# buoi121.net
KiCad netlist of a schematic drawn in Altium Designer
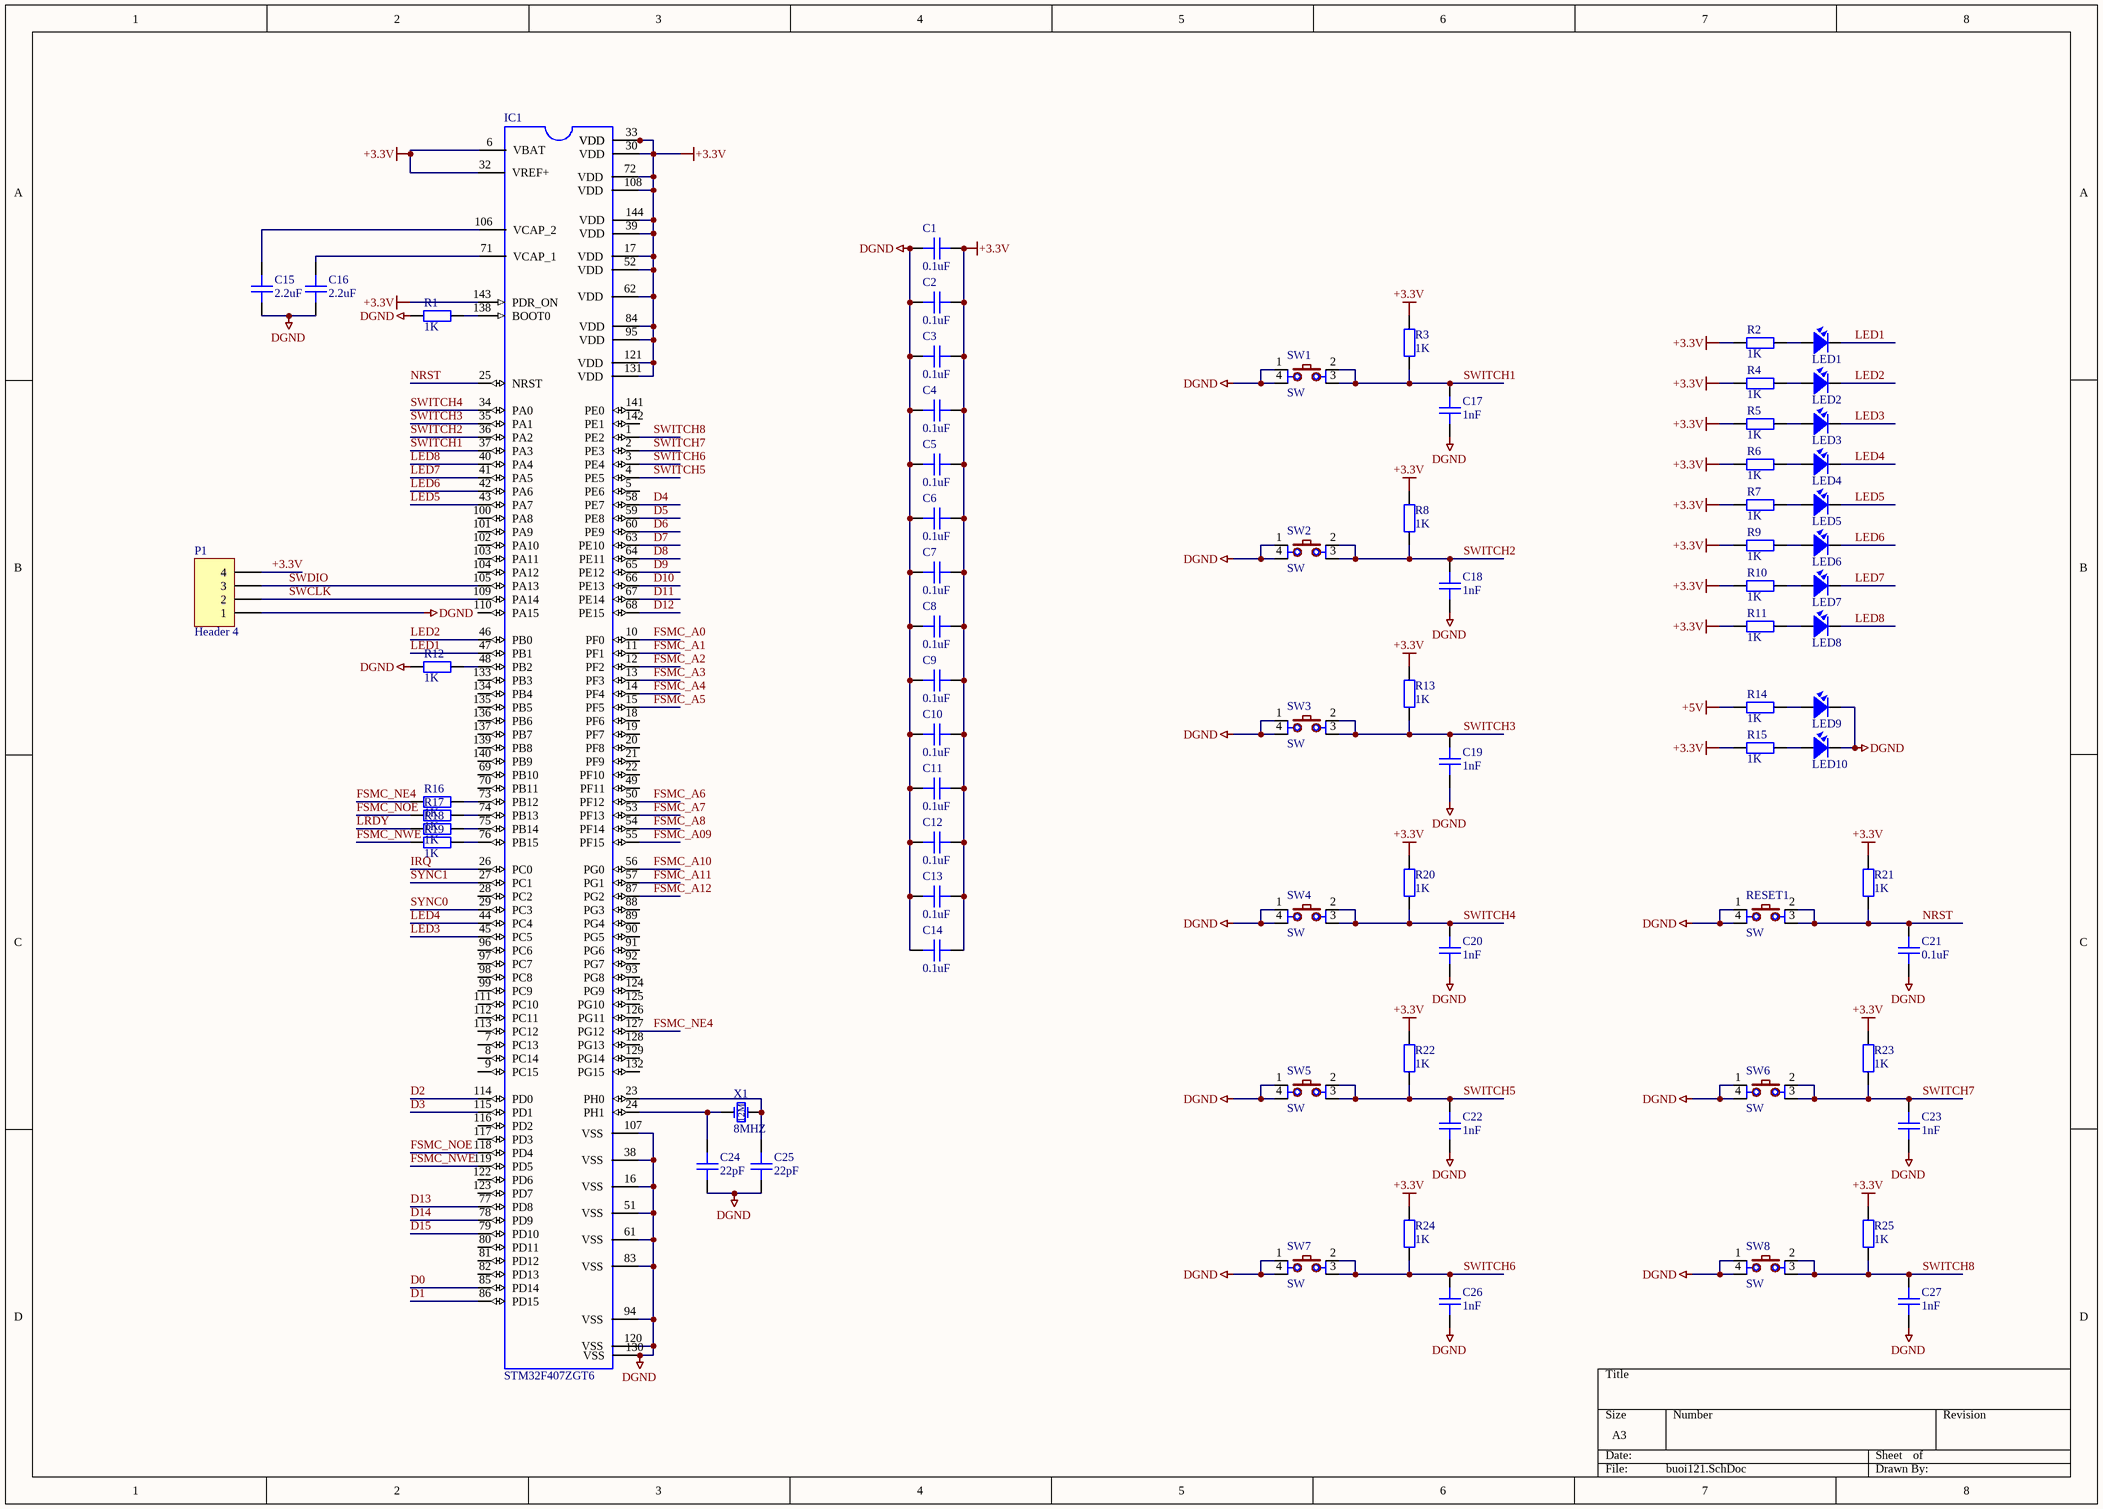
[diagram p0: buoi121.SchDoc]

(export (version "E")
  (design (tool "Eeschema 10.0.6"))
  (components
    (comp (ref "C1")
      (value "0.1uF")
      (footprint "CAPC-0603 (1608)")
      (description "CAP CER 0.1uF 50V 10% X7R 0603")
      (fields (field (name "MPN") "C0603C104K5RACTU"))
      (libsource (lib "BYTECH_HW_LIB_2019 (1)") (part "C0603C104K5RACTU"))
    )
    (comp (ref "C2")
      (value "0.1uF")
      (footprint "CAPC-0603 (1608)")
      (description "CAP CER 0.1uF 50V 10% X7R 0603")
      (fields (field (name "MPN") "C0603C104K5RACTU"))
      (libsource (lib "BYTECH_HW_LIB_2019 (1)") (part "C0603C104K5RACTU"))
    )
    (comp (ref "C3")
      (value "0.1uF")
      (footprint "CAPC-0603 (1608)")
      (description "CAP CER 0.1uF 50V 10% X7R 0603")
      (fields (field (name "MPN") "C0603C104K5RACTU"))
      (libsource (lib "BYTECH_HW_LIB_2019 (1)") (part "C0603C104K5RACTU"))
    )
    (comp (ref "C4")
      (value "0.1uF")
      (footprint "CAPC-0603 (1608)")
      (description "CAP CER 0.1uF 50V 10% X7R 0603")
      (fields (field (name "MPN") "C0603C104K5RACTU"))
      (libsource (lib "BYTECH_HW_LIB_2019 (1)") (part "C0603C104K5RACTU"))
    )
    (comp (ref "C5")
      (value "0.1uF")
      (footprint "CAPC-0603 (1608)")
      (description "CAP CER 0.1uF 50V 10% X7R 0603")
      (fields (field (name "MPN") "C0603C104K5RACTU"))
      (libsource (lib "BYTECH_HW_LIB_2019 (1)") (part "C0603C104K5RACTU"))
    )
    (comp (ref "C6")
      (value "0.1uF")
      (footprint "CAPC-0603 (1608)")
      (description "CAP CER 0.1uF 50V 10% X7R 0603")
      (fields (field (name "MPN") "C0603C104K5RACTU"))
      (libsource (lib "BYTECH_HW_LIB_2019 (1)") (part "C0603C104K5RACTU"))
    )
    (comp (ref "C7")
      (value "0.1uF")
      (footprint "CAPC-0603 (1608)")
      (description "CAP CER 0.1uF 50V 10% X7R 0603")
      (fields (field (name "MPN") "C0603C104K5RACTU"))
      (libsource (lib "BYTECH_HW_LIB_2019 (1)") (part "C0603C104K5RACTU"))
    )
    (comp (ref "C8")
      (value "0.1uF")
      (footprint "CAPC-0603 (1608)")
      (description "CAP CER 0.1uF 50V 10% X7R 0603")
      (fields (field (name "MPN") "C0603C104K5RACTU"))
      (libsource (lib "BYTECH_HW_LIB_2019 (1)") (part "C0603C104K5RACTU"))
    )
    (comp (ref "C9")
      (value "0.1uF")
      (footprint "CAPC-0603 (1608)")
      (description "CAP CER 0.1uF 50V 10% X7R 0603")
      (fields (field (name "MPN") "C0603C104K5RACTU"))
      (libsource (lib "BYTECH_HW_LIB_2019 (1)") (part "C0603C104K5RACTU"))
    )
    (comp (ref "C10")
      (value "0.1uF")
      (footprint "CAPC-0603 (1608)")
      (description "CAP CER 0.1uF 50V 10% X7R 0603")
      (fields (field (name "MPN") "C0603C104K5RACTU"))
      (libsource (lib "BYTECH_HW_LIB_2019 (1)") (part "C0603C104K5RACTU"))
    )
    (comp (ref "C11")
      (value "0.1uF")
      (footprint "CAPC-0603 (1608)")
      (description "CAP CER 0.1uF 50V 10% X7R 0603")
      (fields (field (name "MPN") "C0603C104K5RACTU"))
      (libsource (lib "BYTECH_HW_LIB_2019 (1)") (part "C0603C104K5RACTU"))
    )
    (comp (ref "C12")
      (value "0.1uF")
      (footprint "CAPC-0603 (1608)")
      (description "CAP CER 0.1uF 50V 10% X7R 0603")
      (fields (field (name "MPN") "C0603C104K5RACTU"))
      (libsource (lib "BYTECH_HW_LIB_2019 (1)") (part "C0603C104K5RACTU"))
    )
    (comp (ref "C13")
      (value "0.1uF")
      (footprint "CAPC-0603 (1608)")
      (description "CAP CER 0.1uF 50V 10% X7R 0603")
      (fields (field (name "MPN") "C0603C104K5RACTU"))
      (libsource (lib "BYTECH_HW_LIB_2019 (1)") (part "C0603C104K5RACTU"))
    )
    (comp (ref "C14")
      (value "0.1uF")
      (footprint "CAPC-0603 (1608)")
      (description "CAP CER 0.1uF 50V 10% X7R 0603")
      (fields (field (name "MPN") "C0603C104K5RACTU"))
      (libsource (lib "BYTECH_HW_LIB_2019 (1)") (part "C0603C104K5RACTU"))
    )
    (comp (ref "C15")
      (value "2.2uF")
      (footprint "CAPC-0603 (1608)")
      (description "CAP CER 0.1uF 50V 10% X7R 0603")
      (fields (field (name "MPN") "C0603C104K5RACTU"))
      (libsource (lib "BYTECH_HW_LIB_2019 (1)") (part "C0603C104K5RACTU"))
    )
    (comp (ref "C16")
      (value "2.2uF")
      (footprint "CAPC-0603 (1608)")
      (description "CAP CER 0.1uF 50V 10% X7R 0603")
      (fields (field (name "MPN") "C0603C104K5RACTU"))
      (libsource (lib "BYTECH_HW_LIB_2019 (1)") (part "C0603C104K5RACTU"))
    )
    (comp (ref "C17")
      (value "1nF")
      (footprint "CAPC-0603 (1608)")
      (description "CAP CER 0.1uF 50V 10% X7R 0603")
      (fields (field (name "MPN") "C0603C104K5RACTU"))
      (libsource (lib "BYTECH_HW_LIB_2019 (1)") (part "C0603C104K5RACTU"))
    )
    (comp (ref "C18")
      (value "1nF")
      (footprint "CAPC-0603 (1608)")
      (description "CAP CER 0.1uF 50V 10% X7R 0603")
      (fields (field (name "MPN") "C0603C104K5RACTU"))
      (libsource (lib "BYTECH_HW_LIB_2019 (1)") (part "C0603C104K5RACTU"))
    )
    (comp (ref "C19")
      (value "1nF")
      (footprint "CAPC-0603 (1608)")
      (description "CAP CER 0.1uF 50V 10% X7R 0603")
      (fields (field (name "MPN") "C0603C104K5RACTU"))
      (libsource (lib "BYTECH_HW_LIB_2019 (1)") (part "C0603C104K5RACTU"))
    )
    (comp (ref "C20")
      (value "1nF")
      (footprint "CAPC-0603 (1608)")
      (description "CAP CER 0.1uF 50V 10% X7R 0603")
      (fields (field (name "MPN") "C0603C104K5RACTU"))
      (libsource (lib "BYTECH_HW_LIB_2019 (1)") (part "C0603C104K5RACTU"))
    )
    (comp (ref "C21")
      (value "0.1uF")
      (footprint "CAPC-0603 (1608)")
      (description "CAP CER 0.1uF 50V 10% X7R 0603")
      (fields (field (name "MPN") "C0603C104K5RACTU"))
      (libsource (lib "BYTECH_HW_LIB_2019 (1)") (part "C0603C104K5RACTU"))
    )
    (comp (ref "C22")
      (value "1nF")
      (footprint "CAPC-0603 (1608)")
      (description "CAP CER 0.1uF 50V 10% X7R 0603")
      (fields (field (name "MPN") "C0603C104K5RACTU"))
      (libsource (lib "BYTECH_HW_LIB_2019 (1)") (part "C0603C104K5RACTU"))
    )
    (comp (ref "C23")
      (value "1nF")
      (footprint "CAPC-0603 (1608)")
      (description "CAP CER 0.1uF 50V 10% X7R 0603")
      (fields (field (name "MPN") "C0603C104K5RACTU"))
      (libsource (lib "BYTECH_HW_LIB_2019 (1)") (part "C0603C104K5RACTU"))
    )
    (comp (ref "C24")
      (value "22pF")
      (footprint "CAPC-0603 (1608)")
      (description "CAP CER 0.1uF 50V 10% X7R 0603")
      (fields (field (name "MPN") "C0603C104K5RACTU"))
      (libsource (lib "BYTECH_HW_LIB_2019 (1)") (part "C0603C104K5RACTU"))
    )
    (comp (ref "C25")
      (value "22pF")
      (footprint "CAPC-0603 (1608)")
      (description "CAP CER 0.1uF 50V 10% X7R 0603")
      (fields (field (name "MPN") "C0603C104K5RACTU"))
      (libsource (lib "BYTECH_HW_LIB_2019 (1)") (part "C0603C104K5RACTU"))
    )
    (comp (ref "C26")
      (value "1nF")
      (footprint "CAPC-0603 (1608)")
      (description "CAP CER 0.1uF 50V 10% X7R 0603")
      (fields (field (name "MPN") "C0603C104K5RACTU"))
      (libsource (lib "BYTECH_HW_LIB_2019 (1)") (part "C0603C104K5RACTU"))
    )
    (comp (ref "C27")
      (value "1nF")
      (footprint "CAPC-0603 (1608)")
      (description "CAP CER 0.1uF 50V 10% X7R 0603")
      (fields (field (name "MPN") "C0603C104K5RACTU"))
      (libsource (lib "BYTECH_HW_LIB_2019 (1)") (part "C0603C104K5RACTU"))
    )
    (comp (ref "IC1")
      (value "STM32F407ZGT6")
      (footprint "PCBComponent_1 - duplicate")
      (libsource (lib "STM32F407ZGT6") (part "STM32"))
    )
    (comp (ref "LED1")
      (value "LED")
      (footprint "LED_0603_BLUE")
      (libsource (lib "TechMT.VN_Lib_Project v2") (part "LED SMD"))
    )
    (comp (ref "LED2")
      (value "LED")
      (footprint "LED_0603_BLUE")
      (libsource (lib "TechMT.VN_Lib_Project v2") (part "LED SMD"))
    )
    (comp (ref "LED3")
      (value "LED")
      (footprint "LED_0603_BLUE")
      (libsource (lib "TechMT.VN_Lib_Project v2") (part "LED SMD"))
    )
    (comp (ref "LED4")
      (value "LED")
      (footprint "LED_0603_BLUE")
      (libsource (lib "TechMT.VN_Lib_Project v2") (part "LED SMD"))
    )
    (comp (ref "LED5")
      (value "LED")
      (footprint "LED_0603_BLUE")
      (libsource (lib "TechMT.VN_Lib_Project v2") (part "LED SMD"))
    )
    (comp (ref "LED6")
      (value "LED")
      (footprint "LED_0603_BLUE")
      (libsource (lib "TechMT.VN_Lib_Project v2") (part "LED SMD"))
    )
    (comp (ref "LED7")
      (value "LED")
      (footprint "LED_0603_BLUE")
      (libsource (lib "TechMT.VN_Lib_Project v2") (part "LED SMD"))
    )
    (comp (ref "LED8")
      (value "LED")
      (footprint "LED_0603_BLUE")
      (libsource (lib "TechMT.VN_Lib_Project v2") (part "LED SMD"))
    )
    (comp (ref "LED9")
      (value "LED")
      (footprint "LED_0603_BLUE")
      (libsource (lib "TechMT.VN_Lib_Project v2") (part "LED SMD"))
    )
    (comp (ref "LED10")
      (value "LED")
      (footprint "LED_0603_BLUE")
      (libsource (lib "TechMT.VN_Lib_Project v2") (part "LED SMD"))
    )
    (comp (ref "P1")
      (value "Header 4")
      (footprint "HDR1X4")
      (description "Header, 4-Pin")
      (fields (field (name "PUBLISHER") "Altium Limited"))
      (libsource (lib "My Library") (part "Header 4"))
    )
    (comp (ref "R1")
      (value "1K")
      (footprint "RESC-0603 (1608)")
      (description "RES SMD 2.2K OHM 1% 1/10W 0603")
      (fields (field (name "MPN") "CRCW06032K20FKEA"))
      (libsource (lib "") (part "CRCW06032K20FKEA_1"))
    )
    (comp (ref "R2")
      (value "1K")
      (footprint "RESC-0603 (1608)")
      (description "RES SMD 2.2K OHM 1% 1/10W 0603")
      (fields (field (name "MPN") "CRCW06032K20FKEA"))
      (libsource (lib "BYTECH_HW_LIB_2019 (1)") (part "CRCW06032K20FKEA"))
    )
    (comp (ref "R3")
      (value "1K")
      (footprint "RESC-0603 (1608)")
      (description "RES SMD 2.2K OHM 1% 1/10W 0603")
      (fields (field (name "MPN") "CRCW06032K20FKEA"))
      (libsource (lib "") (part "CRCW06032K20FKEA_2"))
    )
    (comp (ref "R4")
      (value "1K")
      (footprint "RESC-0603 (1608)")
      (description "RES SMD 2.2K OHM 1% 1/10W 0603")
      (fields (field (name "MPN") "CRCW06032K20FKEA"))
      (libsource (lib "BYTECH_HW_LIB_2019 (1)") (part "CRCW06032K20FKEA"))
    )
    (comp (ref "R5")
      (value "1K")
      (footprint "RESC-0603 (1608)")
      (description "RES SMD 2.2K OHM 1% 1/10W 0603")
      (fields (field (name "MPN") "CRCW06032K20FKEA"))
      (libsource (lib "BYTECH_HW_LIB_2019 (1)") (part "CRCW06032K20FKEA"))
    )
    (comp (ref "R6")
      (value "1K")
      (footprint "RESC-0603 (1608)")
      (description "RES SMD 2.2K OHM 1% 1/10W 0603")
      (fields (field (name "MPN") "CRCW06032K20FKEA"))
      (libsource (lib "BYTECH_HW_LIB_2019 (1)") (part "CRCW06032K20FKEA"))
    )
    (comp (ref "R7")
      (value "1K")
      (footprint "RESC-0603 (1608)")
      (description "RES SMD 2.2K OHM 1% 1/10W 0603")
      (fields (field (name "MPN") "CRCW06032K20FKEA"))
      (libsource (lib "BYTECH_HW_LIB_2019 (1)") (part "CRCW06032K20FKEA"))
    )
    (comp (ref "R8")
      (value "1K")
      (footprint "RESC-0603 (1608)")
      (description "RES SMD 2.2K OHM 1% 1/10W 0603")
      (fields (field (name "MPN") "CRCW06032K20FKEA"))
      (libsource (lib "") (part "CRCW06032K20FKEA_2"))
    )
    (comp (ref "R9")
      (value "1K")
      (footprint "RESC-0603 (1608)")
      (description "RES SMD 2.2K OHM 1% 1/10W 0603")
      (fields (field (name "MPN") "CRCW06032K20FKEA"))
      (libsource (lib "BYTECH_HW_LIB_2019 (1)") (part "CRCW06032K20FKEA"))
    )
    (comp (ref "R10")
      (value "1K")
      (footprint "RESC-0603 (1608)")
      (description "RES SMD 2.2K OHM 1% 1/10W 0603")
      (fields (field (name "MPN") "CRCW06032K20FKEA"))
      (libsource (lib "BYTECH_HW_LIB_2019 (1)") (part "CRCW06032K20FKEA"))
    )
    (comp (ref "R11")
      (value "1K")
      (footprint "RESC-0603 (1608)")
      (description "RES SMD 2.2K OHM 1% 1/10W 0603")
      (fields (field (name "MPN") "CRCW06032K20FKEA"))
      (libsource (lib "BYTECH_HW_LIB_2019 (1)") (part "CRCW06032K20FKEA"))
    )
    (comp (ref "R12")
      (value "1K")
      (footprint "RESC-0603 (1608)")
      (description "RES SMD 2.2K OHM 1% 1/10W 0603")
      (fields (field (name "MPN") "CRCW06032K20FKEA"))
      (libsource (lib "") (part "CRCW06032K20FKEA_1"))
    )
    (comp (ref "R13")
      (value "1K")
      (footprint "RESC-0603 (1608)")
      (description "RES SMD 2.2K OHM 1% 1/10W 0603")
      (fields (field (name "MPN") "CRCW06032K20FKEA"))
      (libsource (lib "") (part "CRCW06032K20FKEA_2"))
    )
    (comp (ref "R14")
      (value "1K")
      (footprint "RESC-0603 (1608)")
      (description "RES SMD 2.2K OHM 1% 1/10W 0603")
      (fields (field (name "MPN") "CRCW06032K20FKEA"))
      (libsource (lib "BYTECH_HW_LIB_2019 (1)") (part "CRCW06032K20FKEA"))
    )
    (comp (ref "R15")
      (value "1K")
      (footprint "RESC-0603 (1608)")
      (description "RES SMD 2.2K OHM 1% 1/10W 0603")
      (fields (field (name "MPN") "CRCW06032K20FKEA"))
      (libsource (lib "BYTECH_HW_LIB_2019 (1)") (part "CRCW06032K20FKEA"))
    )
    (comp (ref "R16")
      (value "1K")
      (footprint "RESC-0603 (1608)")
      (description "RES SMD 2.2K OHM 1% 1/10W 0603")
      (fields (field (name "MPN") "CRCW06032K20FKEA"))
      (libsource (lib "") (part "CRCW06032K20FKEA_1"))
    )
    (comp (ref "R17")
      (value "1K")
      (footprint "RESC-0603 (1608)")
      (description "RES SMD 2.2K OHM 1% 1/10W 0603")
      (fields (field (name "MPN") "CRCW06032K20FKEA"))
      (libsource (lib "") (part "CRCW06032K20FKEA_1"))
    )
    (comp (ref "R18")
      (value "1K")
      (footprint "RESC-0603 (1608)")
      (description "RES SMD 2.2K OHM 1% 1/10W 0603")
      (fields (field (name "MPN") "CRCW06032K20FKEA"))
      (libsource (lib "") (part "CRCW06032K20FKEA_1"))
    )
    (comp (ref "R19")
      (value "1K")
      (footprint "RESC-0603 (1608)")
      (description "RES SMD 2.2K OHM 1% 1/10W 0603")
      (fields (field (name "MPN") "CRCW06032K20FKEA"))
      (libsource (lib "") (part "CRCW06032K20FKEA_1"))
    )
    (comp (ref "R20")
      (value "1K")
      (footprint "RESC-0603 (1608)")
      (description "RES SMD 2.2K OHM 1% 1/10W 0603")
      (fields (field (name "MPN") "CRCW06032K20FKEA"))
      (libsource (lib "") (part "CRCW06032K20FKEA_2"))
    )
    (comp (ref "R21")
      (value "1K")
      (footprint "RESC-0603 (1608)")
      (description "RES SMD 2.2K OHM 1% 1/10W 0603")
      (fields (field (name "MPN") "CRCW06032K20FKEA"))
      (libsource (lib "") (part "CRCW06032K20FKEA_2"))
    )
    (comp (ref "R22")
      (value "1K")
      (footprint "RESC-0603 (1608)")
      (description "RES SMD 2.2K OHM 1% 1/10W 0603")
      (fields (field (name "MPN") "CRCW06032K20FKEA"))
      (libsource (lib "") (part "CRCW06032K20FKEA_2"))
    )
    (comp (ref "R23")
      (value "1K")
      (footprint "RESC-0603 (1608)")
      (description "RES SMD 2.2K OHM 1% 1/10W 0603")
      (fields (field (name "MPN") "CRCW06032K20FKEA"))
      (libsource (lib "") (part "CRCW06032K20FKEA_2"))
    )
    (comp (ref "R24")
      (value "1K")
      (footprint "RESC-0603 (1608)")
      (description "RES SMD 2.2K OHM 1% 1/10W 0603")
      (fields (field (name "MPN") "CRCW06032K20FKEA"))
      (libsource (lib "") (part "CRCW06032K20FKEA_2"))
    )
    (comp (ref "R25")
      (value "1K")
      (footprint "RESC-0603 (1608)")
      (description "RES SMD 2.2K OHM 1% 1/10W 0603")
      (fields (field (name "MPN") "CRCW06032K20FKEA"))
      (libsource (lib "") (part "CRCW06032K20FKEA_2"))
    )
    (comp (ref "RESET1")
      (value "SW")
      (footprint "SW2-SMD")
      (description "Switch button 4 pin")
      (libsource (lib "TechMT.VN_Lib_Project v2") (part "SW4"))
    )
    (comp (ref "SW1")
      (value "SW")
      (footprint "SW2-SMD")
      (description "Switch button 4 pin")
      (libsource (lib "TechMT.VN_Lib_Project v2") (part "SW4"))
    )
    (comp (ref "SW2")
      (value "SW")
      (footprint "SW2-SMD")
      (description "Switch button 4 pin")
      (libsource (lib "TechMT.VN_Lib_Project v2") (part "SW4"))
    )
    (comp (ref "SW3")
      (value "SW")
      (footprint "SW2-SMD")
      (description "Switch button 4 pin")
      (libsource (lib "TechMT.VN_Lib_Project v2") (part "SW4"))
    )
    (comp (ref "SW4")
      (value "SW")
      (footprint "SW2-SMD")
      (description "Switch button 4 pin")
      (libsource (lib "TechMT.VN_Lib_Project v2") (part "SW4"))
    )
    (comp (ref "SW5")
      (value "SW")
      (footprint "SW2-SMD")
      (description "Switch button 4 pin")
      (libsource (lib "TechMT.VN_Lib_Project v2") (part "SW4"))
    )
    (comp (ref "SW6")
      (value "SW")
      (footprint "SW2-SMD")
      (description "Switch button 4 pin")
      (libsource (lib "TechMT.VN_Lib_Project v2") (part "SW4"))
    )
    (comp (ref "SW7")
      (value "SW")
      (footprint "SW2-SMD")
      (description "Switch button 4 pin")
      (libsource (lib "TechMT.VN_Lib_Project v2") (part "SW4"))
    )
    (comp (ref "SW8")
      (value "SW")
      (footprint "SW2-SMD")
      (description "Switch button 4 pin")
      (libsource (lib "TechMT.VN_Lib_Project v2") (part "SW4"))
    )
    (comp (ref "X1")
      (value "8MHZ")
      (footprint "CRYSTAL_ABM3 5x3.2mm")
      (description "CRYSTAL 25.0000MHZ 18pF SMD")
      (fields (field (name "MPN") "ABM3-12.000MHZ-D2Y-T"))
      (libsource (lib "BYTECH_HW_LIB_2019 (1)") (part "ABM3-12.000MHZ-D2Y-T"))
    )
  )
  (nets
    (net (code "1") (name "+3.3V") (class "Default")
      (node (ref "C1") (pin "2") (pinfunction "2_2") (pintype "passive"))
      (node (ref "C10") (pin "2") (pinfunction "2_2") (pintype "passive"))
      (node (ref "C11") (pin "2") (pinfunction "2_2") (pintype "passive"))
      (node (ref "C12") (pin "2") (pinfunction "2_2") (pintype "passive"))
      (node (ref "C13") (pin "2") (pinfunction "2_2") (pintype "passive"))
      (node (ref "C14") (pin "2") (pinfunction "2_2") (pintype "passive"))
      (node (ref "C2") (pin "2") (pinfunction "2_2") (pintype "passive"))
      (node (ref "C3") (pin "2") (pinfunction "2_2") (pintype "passive"))
      (node (ref "C4") (pin "2") (pinfunction "2_2") (pintype "passive"))
      (node (ref "C5") (pin "2") (pinfunction "2_2") (pintype "passive"))
      (node (ref "C6") (pin "2") (pinfunction "2_2") (pintype "passive"))
      (node (ref "C7") (pin "2") (pinfunction "2_2") (pintype "passive"))
      (node (ref "C8") (pin "2") (pinfunction "2_2") (pintype "passive"))
      (node (ref "C9") (pin "2") (pinfunction "2_2") (pintype "passive"))
      (node (ref "IC1") (pin "108") (pinfunction "VDD_108") (pintype "power_in"))
      (node (ref "IC1") (pin "121") (pinfunction "VDD_121") (pintype "power_in"))
      (node (ref "IC1") (pin "131") (pinfunction "VDD_131") (pintype "power_in"))
      (node (ref "IC1") (pin "143") (pinfunction "PDR_ON_143") (pintype "input"))
      (node (ref "IC1") (pin "144") (pinfunction "VDD_144") (pintype "power_in"))
      (node (ref "IC1") (pin "17") (pinfunction "VDD_17") (pintype "power_in"))
      (node (ref "IC1") (pin "30") (pinfunction "VDD_30") (pintype "power_in"))
      (node (ref "IC1") (pin "32") (pinfunction "VREF+_32") (pintype "power_in"))
      (node (ref "IC1") (pin "33") (pinfunction "VDD_33") (pintype "power_in"))
      (node (ref "IC1") (pin "39") (pinfunction "VDD_39") (pintype "power_in"))
      (node (ref "IC1") (pin "52") (pinfunction "VDD_52") (pintype "power_in"))
      (node (ref "IC1") (pin "6") (pinfunction "VBAT_6") (pintype "power_in"))
      (node (ref "IC1") (pin "62") (pinfunction "VDD_62") (pintype "power_in"))
      (node (ref "IC1") (pin "72") (pinfunction "VDD_72") (pintype "power_in"))
      (node (ref "IC1") (pin "84") (pinfunction "VDD_84") (pintype "power_in"))
      (node (ref "IC1") (pin "95") (pinfunction "VDD_95") (pintype "power_in"))
      (node (ref "P1") (pin "4") (pinfunction "4_4") (pintype "passive"))
      (node (ref "R10") (pin "2") (pinfunction "2_2") (pintype "passive"))
      (node (ref "R11") (pin "2") (pinfunction "2_2") (pintype "passive"))
      (node (ref "R13") (pin "1") (pinfunction "1_1") (pintype "passive"))
      (node (ref "R15") (pin "2") (pinfunction "2_2") (pintype "passive"))
      (node (ref "R2") (pin "2") (pinfunction "2_2") (pintype "passive"))
      (node (ref "R20") (pin "1") (pinfunction "1_1") (pintype "passive"))
      (node (ref "R21") (pin "1") (pinfunction "1_1") (pintype "passive"))
      (node (ref "R22") (pin "1") (pinfunction "1_1") (pintype "passive"))
      (node (ref "R23") (pin "1") (pinfunction "1_1") (pintype "passive"))
      (node (ref "R24") (pin "1") (pinfunction "1_1") (pintype "passive"))
      (node (ref "R25") (pin "1") (pinfunction "1_1") (pintype "passive"))
      (node (ref "R3") (pin "1") (pinfunction "1_1") (pintype "passive"))
      (node (ref "R4") (pin "2") (pinfunction "2_2") (pintype "passive"))
      (node (ref "R5") (pin "2") (pinfunction "2_2") (pintype "passive"))
      (node (ref "R6") (pin "2") (pinfunction "2_2") (pintype "passive"))
      (node (ref "R7") (pin "2") (pinfunction "2_2") (pintype "passive"))
      (node (ref "R8") (pin "1") (pinfunction "1_1") (pintype "passive"))
      (node (ref "R9") (pin "2") (pinfunction "2_2") (pintype "passive"))
    )
    (net (code "2") (name "+5V") (class "Default")
      (node (ref "R14") (pin "2") (pinfunction "2_2") (pintype "passive"))
    )
    (net (code "3") (name "/D0") (class "Default")
      (node (ref "IC1") (pin "85") (pinfunction "PD14_85") (pintype "bidirectional"))
    )
    (net (code "4") (name "/D1") (class "Default")
      (node (ref "IC1") (pin "86") (pinfunction "PD15_86") (pintype "bidirectional"))
    )
    (net (code "5") (name "/D2") (class "Default")
      (node (ref "IC1") (pin "114") (pinfunction "PD0_114") (pintype "bidirectional"))
    )
    (net (code "6") (name "/D3") (class "Default")
      (node (ref "IC1") (pin "115") (pinfunction "PD1_115") (pintype "bidirectional"))
    )
    (net (code "7") (name "/D4") (class "Default")
      (node (ref "IC1") (pin "58") (pinfunction "PE7_58") (pintype "bidirectional"))
    )
    (net (code "8") (name "/D5") (class "Default")
      (node (ref "IC1") (pin "59") (pinfunction "PE8_59") (pintype "bidirectional"))
    )
    (net (code "9") (name "/D6") (class "Default")
      (node (ref "IC1") (pin "60") (pinfunction "PE9_60") (pintype "bidirectional"))
    )
    (net (code "10") (name "/D7") (class "Default")
      (node (ref "IC1") (pin "63") (pinfunction "PE10_63") (pintype "bidirectional"))
    )
    (net (code "11") (name "/D8") (class "Default")
      (node (ref "IC1") (pin "64") (pinfunction "PE11_64") (pintype "bidirectional"))
    )
    (net (code "12") (name "/D9") (class "Default")
      (node (ref "IC1") (pin "65") (pinfunction "PE12_65") (pintype "bidirectional"))
    )
    (net (code "13") (name "/D10") (class "Default")
      (node (ref "IC1") (pin "66") (pinfunction "PE13_66") (pintype "bidirectional"))
    )
    (net (code "14") (name "/D11") (class "Default")
      (node (ref "IC1") (pin "67") (pinfunction "PE14_67") (pintype "bidirectional"))
    )
    (net (code "15") (name "/D12") (class "Default")
      (node (ref "IC1") (pin "68") (pinfunction "PE15_68") (pintype "bidirectional"))
    )
    (net (code "16") (name "/D13") (class "Default")
      (node (ref "IC1") (pin "77") (pinfunction "PD8_77") (pintype "bidirectional"))
    )
    (net (code "17") (name "/D14") (class "Default")
      (node (ref "IC1") (pin "78") (pinfunction "PD9_78") (pintype "bidirectional"))
    )
    (net (code "18") (name "/D15") (class "Default")
      (node (ref "IC1") (pin "79") (pinfunction "PD10_79") (pintype "bidirectional"))
    )
    (net (code "19") (name "/FSMC_A0") (class "Default")
      (node (ref "IC1") (pin "10") (pinfunction "PF0_10") (pintype "bidirectional"))
    )
    (net (code "20") (name "/FSMC_A1") (class "Default")
      (node (ref "IC1") (pin "11") (pinfunction "PF1_11") (pintype "bidirectional"))
    )
    (net (code "21") (name "/FSMC_A2") (class "Default")
      (node (ref "IC1") (pin "12") (pinfunction "PF2_12") (pintype "bidirectional"))
    )
    (net (code "22") (name "/FSMC_A3") (class "Default")
      (node (ref "IC1") (pin "13") (pinfunction "PF3_13") (pintype "bidirectional"))
    )
    (net (code "23") (name "/FSMC_A4") (class "Default")
      (node (ref "IC1") (pin "14") (pinfunction "PF4_14") (pintype "bidirectional"))
    )
    (net (code "24") (name "/FSMC_A5") (class "Default")
      (node (ref "IC1") (pin "15") (pinfunction "PF5_15") (pintype "bidirectional"))
    )
    (net (code "25") (name "/FSMC_A6") (class "Default")
      (node (ref "IC1") (pin "50") (pinfunction "PF12_50") (pintype "bidirectional"))
    )
    (net (code "26") (name "/FSMC_A7") (class "Default")
      (node (ref "IC1") (pin "53") (pinfunction "PF13_53") (pintype "bidirectional"))
    )
    (net (code "27") (name "/FSMC_A8") (class "Default")
      (node (ref "IC1") (pin "54") (pinfunction "PF14_54") (pintype "bidirectional"))
    )
    (net (code "28") (name "/FSMC_A09") (class "Default")
      (node (ref "IC1") (pin "55") (pinfunction "PF15_55") (pintype "bidirectional"))
    )
    (net (code "29") (name "/FSMC_A10") (class "Default")
      (node (ref "IC1") (pin "56") (pinfunction "PG0_56") (pintype "bidirectional"))
    )
    (net (code "30") (name "/FSMC_A11") (class "Default")
      (node (ref "IC1") (pin "57") (pinfunction "PG1_57") (pintype "bidirectional"))
    )
    (net (code "31") (name "/FSMC_A12") (class "Default")
      (node (ref "IC1") (pin "87") (pinfunction "PG2_87") (pintype "bidirectional"))
    )
    (net (code "32") (name "/FSMC_NE4") (class "Default")
      (node (ref "IC1") (pin "127") (pinfunction "PG12_127") (pintype "bidirectional"))
      (node (ref "R16") (pin "1") (pinfunction "1_1") (pintype "passive"))
    )
    (net (code "33") (name "/FSMC_NOE") (class "Default")
      (node (ref "IC1") (pin "118") (pinfunction "PD4_118") (pintype "bidirectional"))
      (node (ref "R17") (pin "1") (pinfunction "1_1") (pintype "passive"))
    )
    (net (code "34") (name "/FSMC_NWE") (class "Default")
      (node (ref "IC1") (pin "119") (pinfunction "PD5_119") (pintype "bidirectional"))
      (node (ref "R19") (pin "1") (pinfunction "1_1") (pintype "passive"))
    )
    (net (code "35") (name "/IRQ") (class "Default")
      (node (ref "IC1") (pin "26") (pinfunction "PC0_26") (pintype "bidirectional"))
    )
    (net (code "36") (name "/LED1") (class "Default")
      (node (ref "IC1") (pin "47") (pinfunction "PB1_47") (pintype "bidirectional"))
      (node (ref "LED1") (pin "2") (pinfunction "2_2") (pintype "passive"))
    )
    (net (code "37") (name "/LED2") (class "Default")
      (node (ref "IC1") (pin "46") (pinfunction "PB0_46") (pintype "bidirectional"))
      (node (ref "LED2") (pin "2") (pinfunction "2_2") (pintype "passive"))
    )
    (net (code "38") (name "/LED3") (class "Default")
      (node (ref "IC1") (pin "45") (pinfunction "PC5_45") (pintype "bidirectional"))
      (node (ref "LED3") (pin "2") (pinfunction "2_2") (pintype "passive"))
    )
    (net (code "39") (name "/LED4") (class "Default")
      (node (ref "IC1") (pin "44") (pinfunction "PC4_44") (pintype "bidirectional"))
      (node (ref "LED4") (pin "2") (pinfunction "2_2") (pintype "passive"))
    )
    (net (code "40") (name "/LED5") (class "Default")
      (node (ref "IC1") (pin "43") (pinfunction "PA7_43") (pintype "bidirectional"))
      (node (ref "LED5") (pin "2") (pinfunction "2_2") (pintype "passive"))
    )
    (net (code "41") (name "/LED6") (class "Default")
      (node (ref "IC1") (pin "42") (pinfunction "PA6_42") (pintype "bidirectional"))
      (node (ref "LED6") (pin "2") (pinfunction "2_2") (pintype "passive"))
    )
    (net (code "42") (name "/LED7") (class "Default")
      (node (ref "IC1") (pin "41") (pinfunction "PA5_41") (pintype "bidirectional"))
      (node (ref "LED7") (pin "2") (pinfunction "2_2") (pintype "passive"))
    )
    (net (code "43") (name "/LED8") (class "Default")
      (node (ref "IC1") (pin "40") (pinfunction "PA4_40") (pintype "bidirectional"))
      (node (ref "LED8") (pin "2") (pinfunction "2_2") (pintype "passive"))
    )
    (net (code "44") (name "/LRDY") (class "Default")
      (node (ref "R18") (pin "1") (pinfunction "1_1") (pintype "passive"))
    )
    (net (code "45") (name "/NRST") (class "Default")
      (node (ref "C21") (pin "2") (pinfunction "2_2") (pintype "passive"))
      (node (ref "IC1") (pin "25") (pinfunction "NRST_25") (pintype "bidirectional"))
      (node (ref "R21") (pin "2") (pinfunction "2_2") (pintype "passive"))
      (node (ref "RESET1") (pin "2") (pinfunction "2_2") (pintype "passive"))
      (node (ref "RESET1") (pin "3") (pinfunction "3_3") (pintype "passive"))
    )
    (net (code "46") (name "/SWCLK") (class "Default")
      (node (ref "IC1") (pin "109") (pinfunction "PA14_109") (pintype "bidirectional"))
      (node (ref "P1") (pin "2") (pinfunction "2_2") (pintype "passive"))
    )
    (net (code "47") (name "/SWDIO") (class "Default")
      (node (ref "IC1") (pin "105") (pinfunction "PA13_105") (pintype "bidirectional"))
      (node (ref "P1") (pin "3") (pinfunction "3_3") (pintype "passive"))
    )
    (net (code "48") (name "/SWITCH1") (class "Default")
      (node (ref "C17") (pin "2") (pinfunction "2_2") (pintype "passive"))
      (node (ref "IC1") (pin "37") (pinfunction "PA3_37") (pintype "bidirectional"))
      (node (ref "R3") (pin "2") (pinfunction "2_2") (pintype "passive"))
      (node (ref "SW1") (pin "2") (pinfunction "2_2") (pintype "passive"))
      (node (ref "SW1") (pin "3") (pinfunction "3_3") (pintype "passive"))
    )
    (net (code "49") (name "/SWITCH2") (class "Default")
      (node (ref "C18") (pin "2") (pinfunction "2_2") (pintype "passive"))
      (node (ref "IC1") (pin "36") (pinfunction "PA2_36") (pintype "bidirectional"))
      (node (ref "R8") (pin "2") (pinfunction "2_2") (pintype "passive"))
      (node (ref "SW2") (pin "2") (pinfunction "2_2") (pintype "passive"))
      (node (ref "SW2") (pin "3") (pinfunction "3_3") (pintype "passive"))
    )
    (net (code "50") (name "/SWITCH3") (class "Default")
      (node (ref "C19") (pin "2") (pinfunction "2_2") (pintype "passive"))
      (node (ref "IC1") (pin "35") (pinfunction "PA1_35") (pintype "bidirectional"))
      (node (ref "R13") (pin "2") (pinfunction "2_2") (pintype "passive"))
      (node (ref "SW3") (pin "2") (pinfunction "2_2") (pintype "passive"))
      (node (ref "SW3") (pin "3") (pinfunction "3_3") (pintype "passive"))
    )
    (net (code "51") (name "/SWITCH4") (class "Default")
      (node (ref "C20") (pin "2") (pinfunction "2_2") (pintype "passive"))
      (node (ref "IC1") (pin "34") (pinfunction "PA0_34") (pintype "bidirectional"))
      (node (ref "R20") (pin "2") (pinfunction "2_2") (pintype "passive"))
      (node (ref "SW4") (pin "2") (pinfunction "2_2") (pintype "passive"))
      (node (ref "SW4") (pin "3") (pinfunction "3_3") (pintype "passive"))
    )
    (net (code "52") (name "/SWITCH5") (class "Default")
      (node (ref "C22") (pin "2") (pinfunction "2_2") (pintype "passive"))
      (node (ref "IC1") (pin "4") (pinfunction "PE5_4") (pintype "bidirectional"))
      (node (ref "R22") (pin "2") (pinfunction "2_2") (pintype "passive"))
      (node (ref "SW5") (pin "2") (pinfunction "2_2") (pintype "passive"))
      (node (ref "SW5") (pin "3") (pinfunction "3_3") (pintype "passive"))
    )
    (net (code "53") (name "/SWITCH6") (class "Default")
      (node (ref "C26") (pin "2") (pinfunction "2_2") (pintype "passive"))
      (node (ref "IC1") (pin "3") (pinfunction "PE4_3") (pintype "bidirectional"))
      (node (ref "R24") (pin "2") (pinfunction "2_2") (pintype "passive"))
      (node (ref "SW7") (pin "2") (pinfunction "2_2") (pintype "passive"))
      (node (ref "SW7") (pin "3") (pinfunction "3_3") (pintype "passive"))
    )
    (net (code "54") (name "/SWITCH7") (class "Default")
      (node (ref "C23") (pin "2") (pinfunction "2_2") (pintype "passive"))
      (node (ref "IC1") (pin "2") (pinfunction "PE3_2") (pintype "bidirectional"))
      (node (ref "R23") (pin "2") (pinfunction "2_2") (pintype "passive"))
      (node (ref "SW6") (pin "2") (pinfunction "2_2") (pintype "passive"))
      (node (ref "SW6") (pin "3") (pinfunction "3_3") (pintype "passive"))
    )
    (net (code "55") (name "/SWITCH8") (class "Default")
      (node (ref "C27") (pin "2") (pinfunction "2_2") (pintype "passive"))
      (node (ref "IC1") (pin "1") (pinfunction "PE2_1") (pintype "bidirectional"))
      (node (ref "R25") (pin "2") (pinfunction "2_2") (pintype "passive"))
      (node (ref "SW8") (pin "2") (pinfunction "2_2") (pintype "passive"))
      (node (ref "SW8") (pin "3") (pinfunction "3_3") (pintype "passive"))
    )
    (net (code "56") (name "/SYNC0") (class "Default")
      (node (ref "IC1") (pin "29") (pinfunction "PC3_29") (pintype "bidirectional"))
    )
    (net (code "57") (name "/SYNC1") (class "Default")
      (node (ref "IC1") (pin "27") (pinfunction "PC1_27") (pintype "bidirectional"))
    )
    (net (code "58") (name "DGND") (class "Default")
      (node (ref "C1") (pin "1") (pinfunction "1_1") (pintype "passive"))
      (node (ref "C10") (pin "1") (pinfunction "1_1") (pintype "passive"))
      (node (ref "C11") (pin "1") (pinfunction "1_1") (pintype "passive"))
      (node (ref "C12") (pin "1") (pinfunction "1_1") (pintype "passive"))
      (node (ref "C13") (pin "1") (pinfunction "1_1") (pintype "passive"))
      (node (ref "C14") (pin "1") (pinfunction "1_1") (pintype "passive"))
      (node (ref "C15") (pin "1") (pinfunction "1_1") (pintype "passive"))
      (node (ref "C16") (pin "1") (pinfunction "1_1") (pintype "passive"))
      (node (ref "C17") (pin "1") (pinfunction "1_1") (pintype "passive"))
      (node (ref "C18") (pin "1") (pinfunction "1_1") (pintype "passive"))
      (node (ref "C19") (pin "1") (pinfunction "1_1") (pintype "passive"))
      (node (ref "C2") (pin "1") (pinfunction "1_1") (pintype "passive"))
      (node (ref "C20") (pin "1") (pinfunction "1_1") (pintype "passive"))
      (node (ref "C21") (pin "1") (pinfunction "1_1") (pintype "passive"))
      (node (ref "C22") (pin "1") (pinfunction "1_1") (pintype "passive"))
      (node (ref "C23") (pin "1") (pinfunction "1_1") (pintype "passive"))
      (node (ref "C24") (pin "1") (pinfunction "1_1") (pintype "passive"))
      (node (ref "C25") (pin "1") (pinfunction "1_1") (pintype "passive"))
      (node (ref "C26") (pin "1") (pinfunction "1_1") (pintype "passive"))
      (node (ref "C27") (pin "1") (pinfunction "1_1") (pintype "passive"))
      (node (ref "C3") (pin "1") (pinfunction "1_1") (pintype "passive"))
      (node (ref "C4") (pin "1") (pinfunction "1_1") (pintype "passive"))
      (node (ref "C5") (pin "1") (pinfunction "1_1") (pintype "passive"))
      (node (ref "C6") (pin "1") (pinfunction "1_1") (pintype "passive"))
      (node (ref "C7") (pin "1") (pinfunction "1_1") (pintype "passive"))
      (node (ref "C8") (pin "1") (pinfunction "1_1") (pintype "passive"))
      (node (ref "C9") (pin "1") (pinfunction "1_1") (pintype "passive"))
      (node (ref "IC1") (pin "107") (pinfunction "VSS_107") (pintype "passive"))
      (node (ref "IC1") (pin "120") (pinfunction "VSS_120") (pintype "passive"))
      (node (ref "IC1") (pin "130") (pinfunction "VSS_130") (pintype "passive"))
      (node (ref "IC1") (pin "16") (pinfunction "VSS_16") (pintype "passive"))
      (node (ref "IC1") (pin "38") (pinfunction "VSS_38") (pintype "passive"))
      (node (ref "IC1") (pin "51") (pinfunction "VSS_51") (pintype "passive"))
      (node (ref "IC1") (pin "61") (pinfunction "VSS_61") (pintype "passive"))
      (node (ref "IC1") (pin "83") (pinfunction "VSS_83") (pintype "passive"))
      (node (ref "IC1") (pin "94") (pinfunction "VSS_94") (pintype "passive"))
      (node (ref "LED10") (pin "2") (pinfunction "2_2") (pintype "passive"))
      (node (ref "LED9") (pin "2") (pinfunction "2_2") (pintype "passive"))
      (node (ref "P1") (pin "1") (pinfunction "1_1") (pintype "passive"))
      (node (ref "R1") (pin "1") (pinfunction "1_1") (pintype "passive"))
      (node (ref "R12") (pin "1") (pinfunction "1_1") (pintype "passive"))
      (node (ref "RESET1") (pin "1") (pintype "passive"))
      (node (ref "RESET1") (pin "4") (pinfunction "4_4") (pintype "passive"))
      (node (ref "SW1") (pin "1") (pintype "passive"))
      (node (ref "SW1") (pin "4") (pinfunction "4_4") (pintype "passive"))
      (node (ref "SW2") (pin "1") (pintype "passive"))
      (node (ref "SW2") (pin "4") (pinfunction "4_4") (pintype "passive"))
      (node (ref "SW3") (pin "1") (pintype "passive"))
      (node (ref "SW3") (pin "4") (pinfunction "4_4") (pintype "passive"))
      (node (ref "SW4") (pin "1") (pintype "passive"))
      (node (ref "SW4") (pin "4") (pinfunction "4_4") (pintype "passive"))
      (node (ref "SW5") (pin "1") (pintype "passive"))
      (node (ref "SW5") (pin "4") (pinfunction "4_4") (pintype "passive"))
      (node (ref "SW6") (pin "1") (pintype "passive"))
      (node (ref "SW6") (pin "4") (pinfunction "4_4") (pintype "passive"))
      (node (ref "SW7") (pin "1") (pintype "passive"))
      (node (ref "SW7") (pin "4") (pinfunction "4_4") (pintype "passive"))
      (node (ref "SW8") (pin "1") (pintype "passive"))
      (node (ref "SW8") (pin "4") (pinfunction "4_4") (pintype "passive"))
    )
    (net (code "59") (name "Net-(IC1-BOOT0)") (class "Default")
      (node (ref "IC1") (pin "138") (pinfunction "BOOT0_138") (pintype "input"))
      (node (ref "R1") (pin "2") (pinfunction "2_2") (pintype "passive"))
    )
    (net (code "60") (name "Net-(IC1-PB2)") (class "Default")
      (node (ref "IC1") (pin "48") (pinfunction "PB2_48") (pintype "bidirectional"))
      (node (ref "R12") (pin "2") (pinfunction "2_2") (pintype "passive"))
    )
    (net (code "61") (name "Net-(IC1-PB12)") (class "Default")
      (node (ref "IC1") (pin "73") (pinfunction "PB12_73") (pintype "bidirectional"))
      (node (ref "R16") (pin "2") (pinfunction "2_2") (pintype "passive"))
    )
    (net (code "62") (name "Net-(IC1-PB13)") (class "Default")
      (node (ref "IC1") (pin "74") (pinfunction "PB13_74") (pintype "bidirectional"))
      (node (ref "R17") (pin "2") (pinfunction "2_2") (pintype "passive"))
    )
    (net (code "63") (name "Net-(IC1-PB14)") (class "Default")
      (node (ref "IC1") (pin "75") (pinfunction "PB14_75") (pintype "bidirectional"))
      (node (ref "R18") (pin "2") (pinfunction "2_2") (pintype "passive"))
    )
    (net (code "64") (name "Net-(IC1-PB15)") (class "Default")
      (node (ref "IC1") (pin "76") (pinfunction "PB15_76") (pintype "bidirectional"))
      (node (ref "R19") (pin "2") (pinfunction "2_2") (pintype "passive"))
    )
    (net (code "65") (name "Net-(IC1-PH0)") (class "Default")
      (node (ref "C25") (pin "2") (pinfunction "2_2") (pintype "passive"))
      (node (ref "IC1") (pin "23") (pinfunction "PH0_23") (pintype "bidirectional"))
      (node (ref "X1") (pin "2") (pinfunction "OSC2_2") (pintype "passive"))
    )
    (net (code "66") (name "Net-(IC1-PH1)") (class "Default")
      (node (ref "C24") (pin "2") (pinfunction "2_2") (pintype "passive"))
      (node (ref "IC1") (pin "24") (pinfunction "PH1_24") (pintype "bidirectional"))
      (node (ref "X1") (pin "1") (pinfunction "OSC1_1") (pintype "passive"))
    )
    (net (code "67") (name "Net-(IC1-VCAP_1)") (class "Default")
      (node (ref "C16") (pin "2") (pinfunction "2_2") (pintype "passive"))
      (node (ref "IC1") (pin "71") (pinfunction "VCAP_1_71") (pintype "power_in"))
    )
    (net (code "68") (name "Net-(IC1-VCAP_2)") (class "Default")
      (node (ref "C15") (pin "2") (pinfunction "2_2") (pintype "passive"))
      (node (ref "IC1") (pin "106") (pinfunction "VCAP_2_106") (pintype "power_in"))
    )
    (net (code "69") (name "Net-(LED1-Pad1)") (class "Default")
      (node (ref "LED1") (pin "1") (pinfunction "1_1") (pintype "passive"))
      (node (ref "R2") (pin "1") (pinfunction "1_1") (pintype "passive"))
    )
    (net (code "70") (name "Net-(LED2-Pad1)") (class "Default")
      (node (ref "LED2") (pin "1") (pinfunction "1_1") (pintype "passive"))
      (node (ref "R4") (pin "1") (pinfunction "1_1") (pintype "passive"))
    )
    (net (code "71") (name "Net-(LED3-Pad1)") (class "Default")
      (node (ref "LED3") (pin "1") (pinfunction "1_1") (pintype "passive"))
      (node (ref "R5") (pin "1") (pinfunction "1_1") (pintype "passive"))
    )
    (net (code "72") (name "Net-(LED4-Pad1)") (class "Default")
      (node (ref "LED4") (pin "1") (pinfunction "1_1") (pintype "passive"))
      (node (ref "R6") (pin "1") (pinfunction "1_1") (pintype "passive"))
    )
    (net (code "73") (name "Net-(LED5-Pad1)") (class "Default")
      (node (ref "LED5") (pin "1") (pinfunction "1_1") (pintype "passive"))
      (node (ref "R7") (pin "1") (pinfunction "1_1") (pintype "passive"))
    )
    (net (code "74") (name "Net-(LED6-Pad1)") (class "Default")
      (node (ref "LED6") (pin "1") (pinfunction "1_1") (pintype "passive"))
      (node (ref "R9") (pin "1") (pinfunction "1_1") (pintype "passive"))
    )
    (net (code "75") (name "Net-(LED7-Pad1)") (class "Default")
      (node (ref "LED7") (pin "1") (pinfunction "1_1") (pintype "passive"))
      (node (ref "R10") (pin "1") (pinfunction "1_1") (pintype "passive"))
    )
    (net (code "76") (name "Net-(LED8-Pad1)") (class "Default")
      (node (ref "LED8") (pin "1") (pinfunction "1_1") (pintype "passive"))
      (node (ref "R11") (pin "1") (pinfunction "1_1") (pintype "passive"))
    )
    (net (code "77") (name "Net-(LED9-Pad1)") (class "Default")
      (node (ref "LED9") (pin "1") (pinfunction "1_1") (pintype "passive"))
      (node (ref "R14") (pin "1") (pinfunction "1_1") (pintype "passive"))
    )
    (net (code "78") (name "Net-(LED10-Pad1)") (class "Default")
      (node (ref "LED10") (pin "1") (pinfunction "1_1") (pintype "passive"))
      (node (ref "R15") (pin "1") (pinfunction "1_1") (pintype "passive"))
    )
    (net (code "79") (name "unconnected-(IC1-PA8-Pad100)") (class "Default")
      (node (ref "IC1") (pin "100") (pinfunction "PA8_100") (pintype "bidirectional"))
    )
    (net (code "80") (name "unconnected-(IC1-PA9-Pad101)") (class "Default")
      (node (ref "IC1") (pin "101") (pinfunction "PA9_101") (pintype "bidirectional"))
    )
    (net (code "81") (name "unconnected-(IC1-PA10-Pad102)") (class "Default")
      (node (ref "IC1") (pin "102") (pinfunction "PA10_102") (pintype "bidirectional"))
    )
    (net (code "82") (name "unconnected-(IC1-PA11-Pad103)") (class "Default")
      (node (ref "IC1") (pin "103") (pinfunction "PA11_103") (pintype "bidirectional"))
    )
    (net (code "83") (name "unconnected-(IC1-PA12-Pad104)") (class "Default")
      (node (ref "IC1") (pin "104") (pinfunction "PA12_104") (pintype "bidirectional"))
    )
    (net (code "84") (name "unconnected-(IC1-PA15-Pad110)") (class "Default")
      (node (ref "IC1") (pin "110") (pinfunction "PA15_110") (pintype "bidirectional"))
    )
    (net (code "85") (name "unconnected-(IC1-PB3-Pad133)") (class "Default")
      (node (ref "IC1") (pin "133") (pinfunction "PB3_133") (pintype "bidirectional"))
    )
    (net (code "86") (name "unconnected-(IC1-PB4-Pad134)") (class "Default")
      (node (ref "IC1") (pin "134") (pinfunction "PB4_134") (pintype "bidirectional"))
    )
    (net (code "87") (name "unconnected-(IC1-PB5-Pad135)") (class "Default")
      (node (ref "IC1") (pin "135") (pinfunction "PB5_135") (pintype "bidirectional"))
    )
    (net (code "88") (name "unconnected-(IC1-PB6-Pad136)") (class "Default")
      (node (ref "IC1") (pin "136") (pinfunction "PB6_136") (pintype "bidirectional"))
    )
    (net (code "89") (name "unconnected-(IC1-PB7-Pad137)") (class "Default")
      (node (ref "IC1") (pin "137") (pinfunction "PB7_137") (pintype "bidirectional"))
    )
    (net (code "90") (name "unconnected-(IC1-PB8-Pad139)") (class "Default")
      (node (ref "IC1") (pin "139") (pinfunction "PB8_139") (pintype "bidirectional"))
    )
    (net (code "91") (name "unconnected-(IC1-PB9-Pad140)") (class "Default")
      (node (ref "IC1") (pin "140") (pinfunction "PB9_140") (pintype "bidirectional"))
    )
    (net (code "92") (name "unconnected-(IC1-PB10-Pad69)") (class "Default")
      (node (ref "IC1") (pin "69") (pinfunction "PB10_69") (pintype "bidirectional"))
    )
    (net (code "93") (name "unconnected-(IC1-PB11-Pad70)") (class "Default")
      (node (ref "IC1") (pin "70") (pinfunction "PB11_70") (pintype "bidirectional"))
    )
    (net (code "94") (name "unconnected-(IC1-PC2-Pad28)") (class "Default")
      (node (ref "IC1") (pin "28") (pinfunction "PC2_28") (pintype "bidirectional"))
    )
    (net (code "95") (name "unconnected-(IC1-PC6-Pad96)") (class "Default")
      (node (ref "IC1") (pin "96") (pinfunction "PC6_96") (pintype "bidirectional"))
    )
    (net (code "96") (name "unconnected-(IC1-PC7-Pad97)") (class "Default")
      (node (ref "IC1") (pin "97") (pinfunction "PC7_97") (pintype "bidirectional"))
    )
    (net (code "97") (name "unconnected-(IC1-PC8-Pad98)") (class "Default")
      (node (ref "IC1") (pin "98") (pinfunction "PC8_98") (pintype "bidirectional"))
    )
    (net (code "98") (name "unconnected-(IC1-PC9-Pad99)") (class "Default")
      (node (ref "IC1") (pin "99") (pinfunction "PC9_99") (pintype "bidirectional"))
    )
    (net (code "99") (name "unconnected-(IC1-PC10-Pad111)") (class "Default")
      (node (ref "IC1") (pin "111") (pinfunction "PC10_111") (pintype "bidirectional"))
    )
    (net (code "100") (name "unconnected-(IC1-PC11-Pad112)") (class "Default")
      (node (ref "IC1") (pin "112") (pinfunction "PC11_112") (pintype "bidirectional"))
    )
    (net (code "101") (name "unconnected-(IC1-PC12-Pad113)") (class "Default")
      (node (ref "IC1") (pin "113") (pinfunction "PC12_113") (pintype "bidirectional"))
    )
    (net (code "102") (name "unconnected-(IC1-PC13-Pad7)") (class "Default")
      (node (ref "IC1") (pin "7") (pinfunction "PC13_7") (pintype "bidirectional"))
    )
    (net (code "103") (name "unconnected-(IC1-PC14-Pad8)") (class "Default")
      (node (ref "IC1") (pin "8") (pinfunction "PC14_8") (pintype "bidirectional"))
    )
    (net (code "104") (name "unconnected-(IC1-PC15-Pad9)") (class "Default")
      (node (ref "IC1") (pin "9") (pinfunction "PC15_9") (pintype "bidirectional"))
    )
    (net (code "105") (name "unconnected-(IC1-PD2-Pad116)") (class "Default")
      (node (ref "IC1") (pin "116") (pinfunction "PD2_116") (pintype "bidirectional"))
    )
    (net (code "106") (name "unconnected-(IC1-PD3-Pad117)") (class "Default")
      (node (ref "IC1") (pin "117") (pinfunction "PD3_117") (pintype "bidirectional"))
    )
    (net (code "107") (name "unconnected-(IC1-PD6-Pad122)") (class "Default")
      (node (ref "IC1") (pin "122") (pinfunction "PD6_122") (pintype "bidirectional"))
    )
    (net (code "108") (name "unconnected-(IC1-PD7-Pad123)") (class "Default")
      (node (ref "IC1") (pin "123") (pinfunction "PD7_123") (pintype "bidirectional"))
    )
    (net (code "109") (name "unconnected-(IC1-PD11-Pad80)") (class "Default")
      (node (ref "IC1") (pin "80") (pinfunction "PD11_80") (pintype "bidirectional"))
    )
    (net (code "110") (name "unconnected-(IC1-PD12-Pad81)") (class "Default")
      (node (ref "IC1") (pin "81") (pinfunction "PD12_81") (pintype "bidirectional"))
    )
    (net (code "111") (name "unconnected-(IC1-PD13-Pad82)") (class "Default")
      (node (ref "IC1") (pin "82") (pinfunction "PD13_82") (pintype "bidirectional"))
    )
    (net (code "112") (name "unconnected-(IC1-PE0-Pad141)") (class "Default")
      (node (ref "IC1") (pin "141") (pinfunction "PE0_141") (pintype "bidirectional"))
    )
    (net (code "113") (name "unconnected-(IC1-PE1-Pad142)") (class "Default")
      (node (ref "IC1") (pin "142") (pinfunction "PE1_142") (pintype "bidirectional"))
    )
    (net (code "114") (name "unconnected-(IC1-PE6-Pad5)") (class "Default")
      (node (ref "IC1") (pin "5") (pinfunction "PE6_5") (pintype "bidirectional"))
    )
    (net (code "115") (name "unconnected-(IC1-PF6-Pad18)") (class "Default")
      (node (ref "IC1") (pin "18") (pinfunction "PF6_18") (pintype "bidirectional"))
    )
    (net (code "116") (name "unconnected-(IC1-PF7-Pad19)") (class "Default")
      (node (ref "IC1") (pin "19") (pinfunction "PF7_19") (pintype "bidirectional"))
    )
    (net (code "117") (name "unconnected-(IC1-PF8-Pad20)") (class "Default")
      (node (ref "IC1") (pin "20") (pinfunction "PF8_20") (pintype "bidirectional"))
    )
    (net (code "118") (name "unconnected-(IC1-PF9-Pad21)") (class "Default")
      (node (ref "IC1") (pin "21") (pinfunction "PF9_21") (pintype "bidirectional"))
    )
    (net (code "119") (name "unconnected-(IC1-PF10-Pad22)") (class "Default")
      (node (ref "IC1") (pin "22") (pinfunction "PF10_22") (pintype "bidirectional"))
    )
    (net (code "120") (name "unconnected-(IC1-PF11-Pad49)") (class "Default")
      (node (ref "IC1") (pin "49") (pinfunction "PF11_49") (pintype "bidirectional"))
    )
    (net (code "121") (name "unconnected-(IC1-PG3-Pad88)") (class "Default")
      (node (ref "IC1") (pin "88") (pinfunction "PG3_88") (pintype "bidirectional"))
    )
    (net (code "122") (name "unconnected-(IC1-PG4-Pad89)") (class "Default")
      (node (ref "IC1") (pin "89") (pinfunction "PG4_89") (pintype "bidirectional"))
    )
    (net (code "123") (name "unconnected-(IC1-PG5-Pad90)") (class "Default")
      (node (ref "IC1") (pin "90") (pinfunction "PG5_90") (pintype "bidirectional"))
    )
    (net (code "124") (name "unconnected-(IC1-PG6-Pad91)") (class "Default")
      (node (ref "IC1") (pin "91") (pinfunction "PG6_91") (pintype "bidirectional"))
    )
    (net (code "125") (name "unconnected-(IC1-PG7-Pad92)") (class "Default")
      (node (ref "IC1") (pin "92") (pinfunction "PG7_92") (pintype "bidirectional"))
    )
    (net (code "126") (name "unconnected-(IC1-PG8-Pad93)") (class "Default")
      (node (ref "IC1") (pin "93") (pinfunction "PG8_93") (pintype "bidirectional"))
    )
    (net (code "127") (name "unconnected-(IC1-PG9-Pad124)") (class "Default")
      (node (ref "IC1") (pin "124") (pinfunction "PG9_124") (pintype "bidirectional"))
    )
    (net (code "128") (name "unconnected-(IC1-PG10-Pad125)") (class "Default")
      (node (ref "IC1") (pin "125") (pinfunction "PG10_125") (pintype "bidirectional"))
    )
    (net (code "129") (name "unconnected-(IC1-PG11-Pad126)") (class "Default")
      (node (ref "IC1") (pin "126") (pinfunction "PG11_126") (pintype "bidirectional"))
    )
    (net (code "130") (name "unconnected-(IC1-PG13-Pad128)") (class "Default")
      (node (ref "IC1") (pin "128") (pinfunction "PG13_128") (pintype "bidirectional"))
    )
    (net (code "131") (name "unconnected-(IC1-PG14-Pad129)") (class "Default")
      (node (ref "IC1") (pin "129") (pinfunction "PG14_129") (pintype "bidirectional"))
    )
    (net (code "132") (name "unconnected-(IC1-PG15-Pad132)") (class "Default")
      (node (ref "IC1") (pin "132") (pinfunction "PG15_132") (pintype "bidirectional"))
    )
  )
)
